# Sheet4_-_Capteurs.net
KiCad netlist of a schematic drawn in Altium Designer
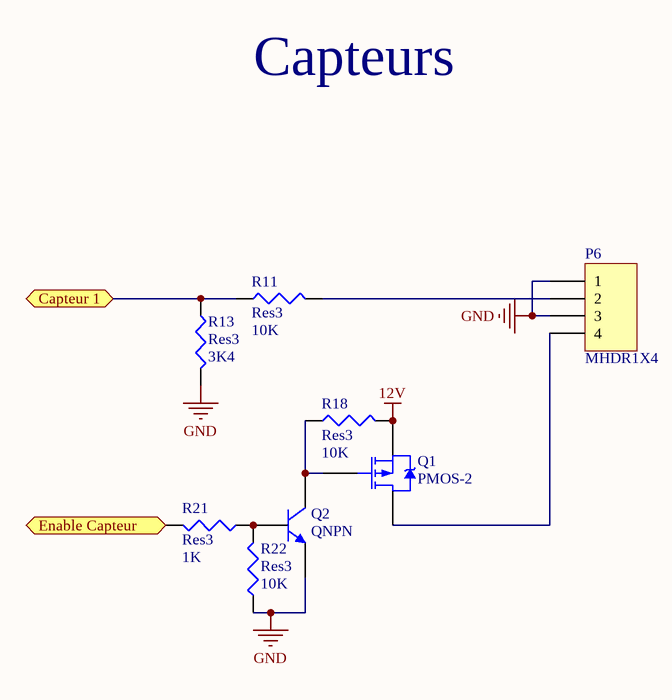
[diagram p0: Sheet4 - Capteurs.SchDoc]

(export (version "E")
  (design (tool "Eeschema 10.0.6"))
  (components
    (comp (ref "P6")
      (value "MHDR1X4")
      (footprint "MHDR1X4")
      (description "Header, 4-Pin")
      (fields (field (name "PUBLISHER") "Altium Limited"))
      (libsource (lib "Miscellaneous Connectors") (part "MHDR1X4"))
    )
    (comp (ref "Q1")
      (value "PMOS-2")
      (footprint "SFM-T3/A4.7V")
      (description "P-Channel Power MOSFET")
      (fields (field (name "PUBLISHER") "Altium Limited"))
      (libsource (lib "Miscellaneous Devices") (part "PMOS-2"))
    )
    (comp (ref "Q2")
      (value "QNPN")
      (footprint "SOT95P240-3N")
      (description "NPN Bipolar Transistor")
      (fields (field (name "PUBLISHER") "Altium Limited"))
      (libsource (lib "Miscellaneous Devices") (part "QNPN"))
    )
    (comp (ref "R11")
      (value "Res3")
      (footprint "RESC1608L")
      (description "Resistor")
      (fields (field (name "ALTIUM_VALUE") "10K") (field (name "PUBLISHER") "Altium Limited"))
      (libsource (lib "Miscellaneous Devices") (part "Res3"))
    )
    (comp (ref "R13")
      (value "Res3")
      (footprint "RESC1608L")
      (description "Resistor")
      (fields (field (name "ALTIUM_VALUE") "3K4") (field (name "PUBLISHER") "Altium Limited"))
      (libsource (lib "Miscellaneous Devices") (part "Res3"))
    )
    (comp (ref "R18")
      (value "Res3")
      (footprint "RESC1608L")
      (description "Resistor")
      (fields (field (name "ALTIUM_VALUE") "10K") (field (name "PUBLISHER") "Altium Limited"))
      (libsource (lib "Miscellaneous Devices") (part "Res3"))
    )
    (comp (ref "R21")
      (value "Res3")
      (footprint "RESC1608L")
      (description "Resistor")
      (fields (field (name "ALTIUM_VALUE") "1K") (field (name "PUBLISHER") "Altium Limited"))
      (libsource (lib "Miscellaneous Devices") (part "Res3"))
    )
    (comp (ref "R22")
      (value "Res3")
      (footprint "RESC1608L")
      (description "Resistor")
      (fields (field (name "ALTIUM_VALUE") "10K") (field (name "PUBLISHER") "Altium Limited"))
      (libsource (lib "Miscellaneous Devices") (part "Res3"))
    )
  )
  (nets
    (net (code "1") (name "/Capteur 1") (class "Default")
      (node (ref "R11") (pin "1") (pinfunction "1_1") (pintype "passive"))
      (node (ref "R13") (pin "1") (pinfunction "1_1") (pintype "passive"))
    )
    (net (code "2") (name "/Enable Capteur") (class "Default")
      (node (ref "R21") (pin "2") (pinfunction "2_2") (pintype "passive"))
    )
    (net (code "3") (name "12V") (class "Default")
      (node (ref "Q1") (pin "3") (pinfunction "S_3") (pintype "passive"))
      (node (ref "R18") (pin "2") (pinfunction "2_2") (pintype "passive"))
    )
    (net (code "4") (name "GND") (class "Default")
      (node (ref "P6") (pin "1") (pinfunction "1_1") (pintype "passive"))
      (node (ref "P6") (pin "3") (pinfunction "3_3") (pintype "passive"))
      (node (ref "Q2") (pin "3") (pinfunction "E_3") (pintype "passive"))
      (node (ref "R13") (pin "2") (pinfunction "2_2") (pintype "passive"))
      (node (ref "R22") (pin "1") (pinfunction "1_1") (pintype "passive"))
    )
    (net (code "5") (name "Net-(P6-Pad2)") (class "Default")
      (node (ref "P6") (pin "2") (pinfunction "2_2") (pintype "passive"))
      (node (ref "R11") (pin "2") (pinfunction "2_2") (pintype "passive"))
    )
    (net (code "6") (name "Net-(Q1-D)") (class "Default")
      (node (ref "P6") (pin "4") (pinfunction "4_4") (pintype "passive"))
      (node (ref "Q1") (pin "2") (pinfunction "D_2") (pintype "passive"))
    )
    (net (code "7") (name "Net-(Q1-G)") (class "Default")
      (node (ref "Q1") (pin "1") (pinfunction "G_1") (pintype "passive"))
      (node (ref "Q2") (pin "1") (pinfunction "C_1") (pintype "passive"))
      (node (ref "R18") (pin "1") (pinfunction "1_1") (pintype "passive"))
    )
    (net (code "8") (name "Net-(Q2-B)") (class "Default")
      (node (ref "Q2") (pin "2") (pinfunction "B_2") (pintype "passive"))
      (node (ref "R21") (pin "1") (pinfunction "1_1") (pintype "passive"))
      (node (ref "R22") (pin "2") (pinfunction "2_2") (pintype "passive"))
    )
  )
)
